# LED_MOUNT_J002609C.net
KiCad netlist of a schematic drawn in EAGLE
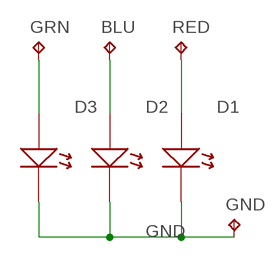
[diagram p0: schematic, sheet 1]

(export (version "E")
  (design (tool "Eeschema 10.0.6"))
  (components
    (comp (ref "BLU")
      (value "TPTP20SQ")
      (footprint "eagle-import:TP20SQ")
      (libsource (lib "eagle-import") (part "TPTP20SQ"))
    )
    (comp (ref "D1")
      (value "LEDLED_SFH4050")
      (footprint "eagle-import:LED_SFH4050")
      (libsource (lib "eagle-import") (part "LEDLED_SFH4050"))
    )
    (comp (ref "D2")
      (value "LEDLED_SFH4050")
      (footprint "eagle-import:LED_SFH4050")
      (libsource (lib "eagle-import") (part "LEDLED_SFH4050"))
    )
    (comp (ref "D3")
      (value "LEDLED_SFH4050")
      (footprint "eagle-import:LED_SFH4050")
      (libsource (lib "eagle-import") (part "LEDLED_SFH4050"))
    )
    (comp (ref "GND")
      (value "TPTP20SQ")
      (footprint "eagle-import:TP20SQ")
      (libsource (lib "eagle-import") (part "TPTP20SQ"))
    )
    (comp (ref "GRN")
      (value "TPTP20SQ")
      (footprint "eagle-import:TP20SQ")
      (libsource (lib "eagle-import") (part "TPTP20SQ"))
    )
    (comp (ref "RED")
      (value "TPTP20SQ")
      (footprint "eagle-import:TP20SQ")
      (libsource (lib "eagle-import") (part "TPTP20SQ"))
    )
  )
  (nets
    (net (code "1") (name "/GND") (class "Default")
      (node (ref "D1") (pin "C") (pinfunction "K_C") (pintype "bidirectional"))
      (node (ref "D2") (pin "C") (pinfunction "K_C") (pintype "bidirectional"))
      (node (ref "D3") (pin "C") (pinfunction "K_C") (pintype "bidirectional"))
      (node (ref "GND") (pin "TP") (pinfunction "TP_TP") (pintype "input"))
    )
    (net (code "2") (name "Net-(BLU-PadTP)") (class "Default")
      (node (ref "BLU") (pin "TP") (pinfunction "TP_TP") (pintype "input"))
      (node (ref "D2") (pin "A") (pinfunction "A_A") (pintype "bidirectional"))
    )
    (net (code "3") (name "Net-(D1-PadA)") (class "Default")
      (node (ref "D1") (pin "A") (pinfunction "A_A") (pintype "bidirectional"))
      (node (ref "RED") (pin "TP") (pinfunction "TP_TP") (pintype "input"))
    )
    (net (code "4") (name "Net-(D3-PadA)") (class "Default")
      (node (ref "D3") (pin "A") (pinfunction "A_A") (pintype "bidirectional"))
      (node (ref "GRN") (pin "TP") (pinfunction "TP_TP") (pintype "input"))
    )
  )
)
